# picoAva-Rev3.net
KiCad netlist of a schematic drawn in EAGLE
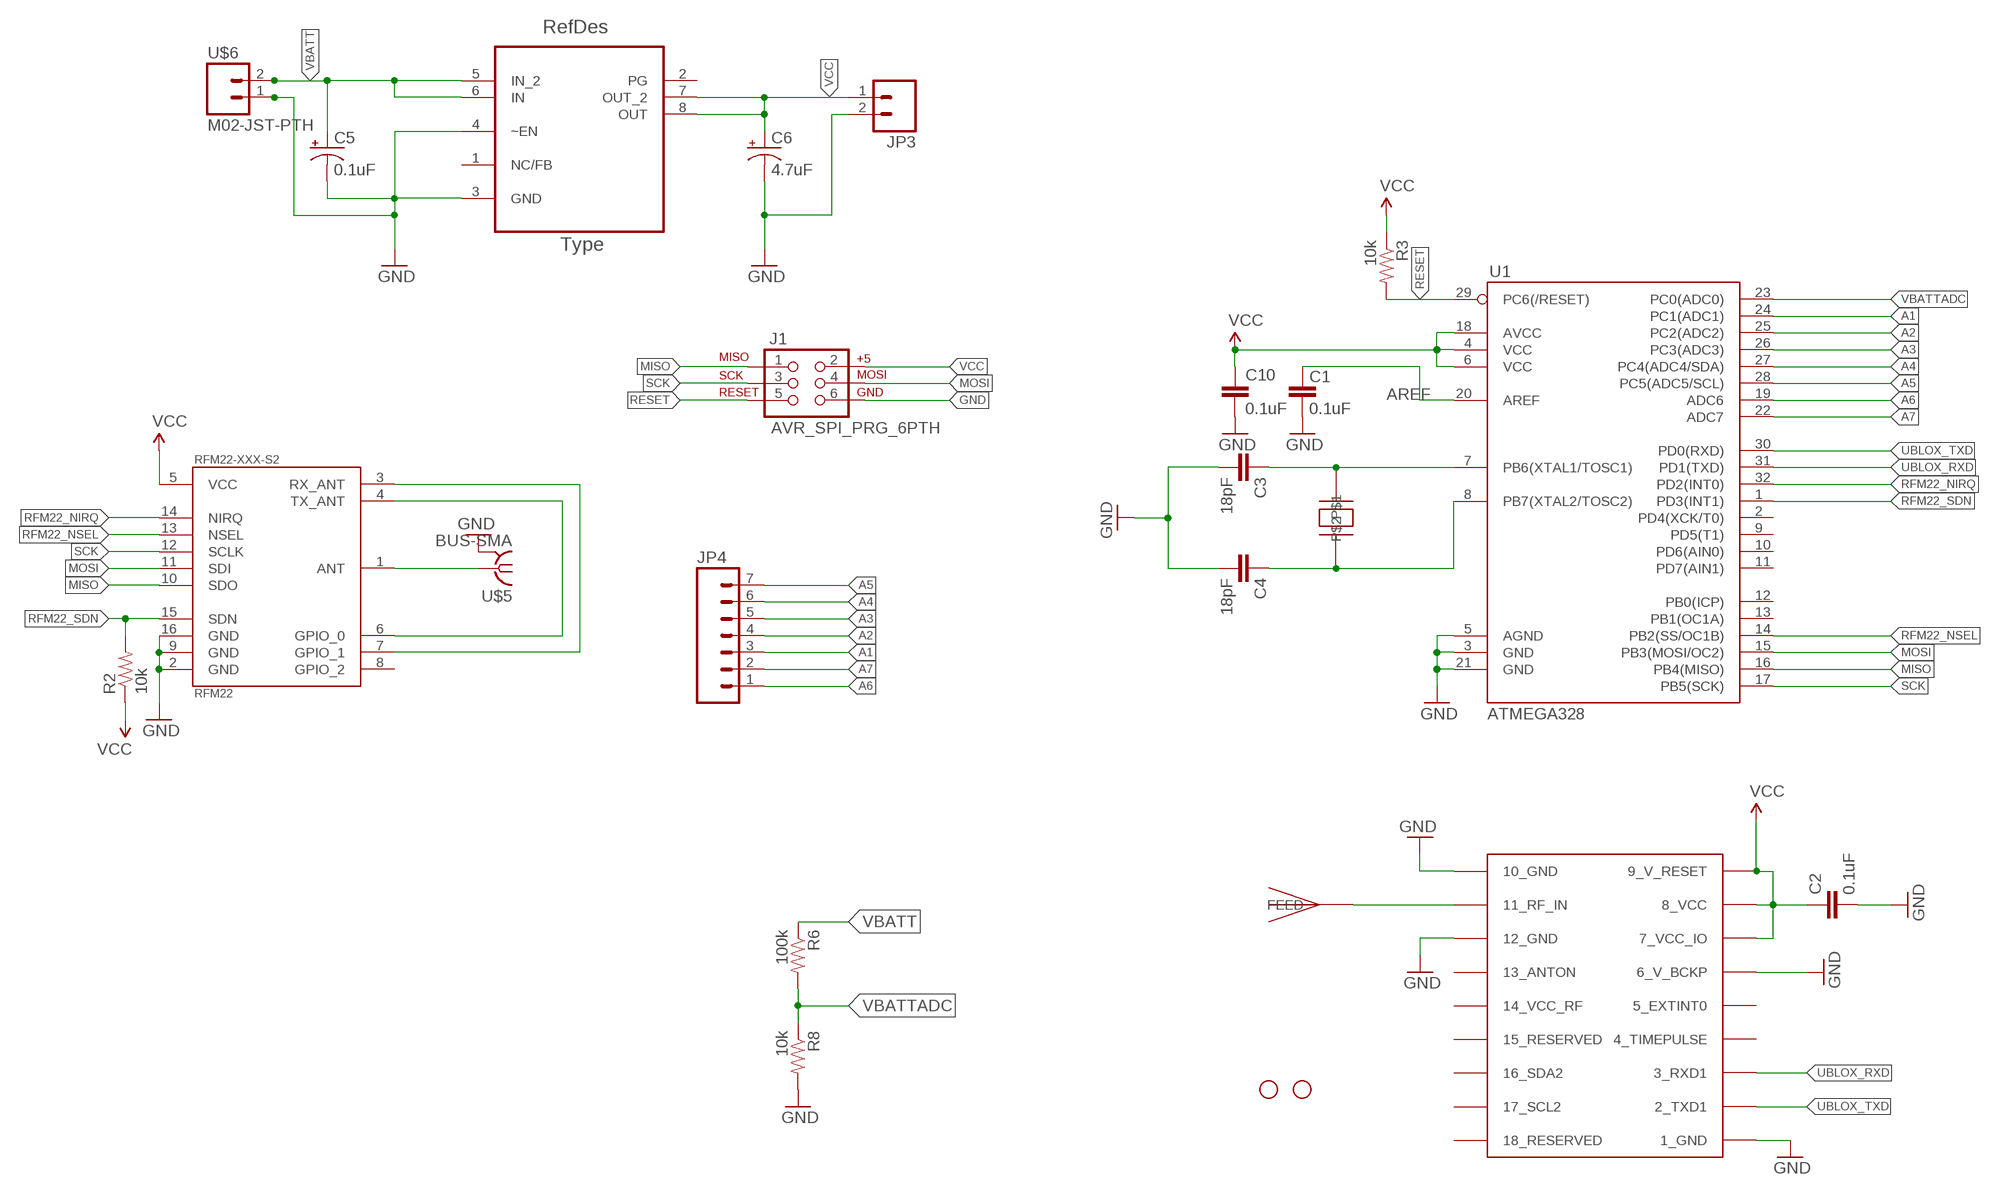
[diagram p0: schematic, sheet 1]

(export (version "E")
  (design (tool "Eeschema 10.0.6"))
  (components
    (comp (ref "C1")
      (value "0.1uF")
      (footprint "eagle-import:0402-CAP")
      (libsource (lib "eagle-import") (part "CAP0402-CAP"))
    )
    (comp (ref "C2")
      (value "0.1uF")
      (footprint "eagle-import:0402-CAP")
      (libsource (lib "eagle-import") (part "CAP0402-CAP"))
    )
    (comp (ref "C3")
      (value "18pF")
      (footprint "eagle-import:0402-CAP")
      (libsource (lib "eagle-import") (part "CAP0402-CAP"))
    )
    (comp (ref "C4")
      (value "18pF")
      (footprint "eagle-import:0402-CAP")
      (libsource (lib "eagle-import") (part "CAP0402-CAP"))
    )
    (comp (ref "C5")
      (value "0.1uF")
      (footprint "eagle-import:EIA3216-KIT")
      (libsource (lib "eagle-import") (part "CAP_POL1206-KIT"))
    )
    (comp (ref "C6")
      (value "4.7uF")
      (footprint "eagle-import:EIA3216-KIT")
      (libsource (lib "eagle-import") (part "CAP_POL1206-KIT"))
    )
    (comp (ref "C10")
      (value "0.1uF")
      (footprint "eagle-import:0402-CAP")
      (libsource (lib "eagle-import") (part "CAP0402-CAP"))
    )
    (comp (ref "J1")
      (value "AVR_SPI_PRG_6PTH")
      (footprint "eagle-import:2X3")
      (libsource (lib "eagle-import") (part "AVR_SPI_PRG_6PTH"))
    )
    (comp (ref "JP1")
      (value "STAND-OFF")
      (footprint "eagle-import:STAND-OFF")
      (libsource (lib "eagle-import") (part "STAND-OFF"))
    )
    (comp (ref "JP2")
      (value "STAND-OFF")
      (footprint "eagle-import:STAND-OFF")
      (libsource (lib "eagle-import") (part "STAND-OFF"))
    )
    (comp (ref "JP3")
      (value "M02PTH")
      (footprint "eagle-import:1X02")
      (libsource (lib "eagle-import") (part "M02PTH"))
    )
    (comp (ref "JP4")
      (value "M07")
      (footprint "eagle-import:1X07")
      (libsource (lib "eagle-import") (part "M07"))
    )
    (comp (ref "R2")
      (value "10k")
      (footprint "eagle-import:0402-RES")
      (libsource (lib "eagle-import") (part "RESISTOR0402-RES"))
    )
    (comp (ref "R3")
      (value "10k")
      (footprint "eagle-import:0402-RES")
      (libsource (lib "eagle-import") (part "RESISTOR0402-RES"))
    )
    (comp (ref "R6")
      (value "100k")
      (footprint "eagle-import:0402-RES")
      (libsource (lib "eagle-import") (part "RESISTOR0402-RES"))
    )
    (comp (ref "R8")
      (value "10k")
      (footprint "eagle-import:0402-RES")
      (libsource (lib "eagle-import") (part "RESISTOR0402-RES"))
    )
    (comp (ref "RFM22-XXX-S2")
      (value "RFM22")
      (footprint "eagle-import:RFM22-XXX-S2")
      (libsource (lib "eagle-import") (part "RFM22"))
    )
    (comp (ref "U$1")
      (value "UBLOX_MAX-6")
      (footprint "eagle-import:UBLOX_MAX-6")
      (libsource (lib "eagle-import") (part "UBLOX_MAX-6"))
    )
    (comp (ref "U$2")
      (value "ABRACON_ABM3_CRYSTAL")
      (footprint "eagle-import:ABRACON_ABM3_CRYSTAL")
      (libsource (lib "eagle-import") (part "ABRACON_ABM3_CRYSTAL"))
    )
    (comp (ref "U$3")
      (value "JTI_ANTENNA-1575AT43A40")
      (footprint "eagle-import:JTI_ANTENNA-1575AT43A40")
      (libsource (lib "eagle-import") (part "JTI_ANTENNA-1575AT43A40"))
    )
    (comp (ref "U$5")
      (value "BUS-SMA")
      (footprint "eagle-import:BUS-SMA")
      (libsource (lib "eagle-import") (part "BUS-SMA"))
    )
    (comp (ref "U$6")
      (value "M02-JST-PTH")
      (footprint "eagle-import:M02-JST-PTH")
      (libsource (lib "eagle-import") (part "M02-JST-PTH"))
    )
    (comp (ref "U1")
      (value "ATMEGA328")
      (footprint "eagle-import:TQFP32-08")
      (libsource (lib "eagle-import") (part "ATMEGA168"))
    )
    (comp (ref "U2")
      (value "TPS76633D")
      (footprint "eagle-import:SOIC127P600X175-8N")
      (libsource (lib "eagle-import") (part "TPS76633D"))
    )
  )
  (nets
    (net (code "1") (name "/AREF") (class "Default")
      (node (ref "C1") (pin "2") (pinfunction "2_2") (pintype "passive"))
      (node (ref "U1") (pin "20") (pinfunction "AREF_20") (pintype "bidirectional"))
    )
    (net (code "2") (name "A1") (class "Default")
      (node (ref "JP4") (pin "3") (pinfunction "3_3") (pintype "passive"))
      (node (ref "U1") (pin "24") (pinfunction "PC1(ADC1)_24") (pintype "bidirectional"))
    )
    (net (code "3") (name "A2") (class "Default")
      (node (ref "JP4") (pin "4") (pinfunction "4_4") (pintype "passive"))
      (node (ref "U1") (pin "25") (pinfunction "PC2(ADC2)_25") (pintype "bidirectional"))
    )
    (net (code "4") (name "A3") (class "Default")
      (node (ref "JP4") (pin "5") (pinfunction "5_5") (pintype "passive"))
      (node (ref "U1") (pin "26") (pinfunction "PC3(ADC3)_26") (pintype "bidirectional"))
    )
    (net (code "5") (name "A4") (class "Default")
      (node (ref "JP4") (pin "6") (pinfunction "6_6") (pintype "passive"))
      (node (ref "U1") (pin "27") (pinfunction "PC4(ADC4/SDA)_27") (pintype "bidirectional"))
    )
    (net (code "6") (name "A5") (class "Default")
      (node (ref "JP4") (pin "7") (pinfunction "7_7") (pintype "passive"))
      (node (ref "U1") (pin "28") (pinfunction "PC5(ADC5/SCL)_28") (pintype "bidirectional"))
    )
    (net (code "7") (name "A6") (class "Default")
      (node (ref "JP4") (pin "1") (pinfunction "1_1") (pintype "passive"))
      (node (ref "U1") (pin "19") (pinfunction "ADC6_19") (pintype "bidirectional"))
    )
    (net (code "8") (name "A7") (class "Default")
      (node (ref "JP4") (pin "2") (pinfunction "2_2") (pintype "passive"))
      (node (ref "U1") (pin "22") (pinfunction "ADC7_22") (pintype "bidirectional"))
    )
    (net (code "9") (name "GND") (class "Default")
      (node (ref "C1") (pin "1") (pinfunction "1_1") (pintype "passive"))
      (node (ref "C10") (pin "2") (pinfunction "2_2") (pintype "passive"))
      (node (ref "C2") (pin "2") (pinfunction "2_2") (pintype "passive"))
      (node (ref "C3") (pin "2") (pinfunction "2_2") (pintype "passive"))
      (node (ref "C4") (pin "2") (pinfunction "2_2") (pintype "passive"))
      (node (ref "C5") (pin "C") (pinfunction "-_C") (pintype "passive"))
      (node (ref "C6") (pin "C") (pinfunction "-_C") (pintype "passive"))
      (node (ref "J1") (pin "6") (pinfunction "6_6") (pintype "passive"))
      (node (ref "JP3") (pin "2") (pinfunction "2_2") (pintype "passive"))
      (node (ref "R8") (pin "2") (pinfunction "2_2") (pintype "passive"))
      (node (ref "RFM22-XXX-S2") (pin "16") (pinfunction "GND_16") (pintype "power_in"))
      (node (ref "RFM22-XXX-S2") (pin "2") (pinfunction "GND_2") (pintype "power_in"))
      (node (ref "RFM22-XXX-S2") (pin "9") (pinfunction "GND_9") (pintype "power_in"))
      (node (ref "U$1") (pin "10_GND") (pinfunction "10_GND_10_GND") (pintype "bidirectional"))
      (node (ref "U$1") (pin "12_GND") (pinfunction "12_GND_12_GND") (pintype "bidirectional"))
      (node (ref "U$1") (pin "1_GND") (pinfunction "1_GND_1_GND") (pintype "bidirectional"))
      (node (ref "U$1") (pin "6_V_BCKP") (pinfunction "6_V_BCKP_6_V_BCKP") (pintype "bidirectional"))
      (node (ref "U$5") (pin "2") (pinfunction "GND_2") (pintype "power_in"))
      (node (ref "U$5") (pin "3") (pinfunction "GND_3") (pintype "power_in"))
      (node (ref "U$5") (pin "4") (pinfunction "GND_4") (pintype "power_in"))
      (node (ref "U$5") (pin "5") (pinfunction "GND_5") (pintype "power_in"))
      (node (ref "U$6") (pin "1") (pinfunction "1_1") (pintype "passive"))
      (node (ref "U1") (pin "21") (pinfunction "GND_21") (pintype "bidirectional"))
      (node (ref "U1") (pin "3") (pinfunction "GND_3") (pintype "bidirectional"))
      (node (ref "U1") (pin "5") (pinfunction "AGND_5") (pintype "bidirectional"))
      (node (ref "U2") (pin "3") (pinfunction "GND_3") (pintype "passive"))
      (node (ref "U2") (pin "4") (pinfunction "~{EN}_4") (pintype "input"))
    )
    (net (code "10") (name "MISO") (class "Default")
      (node (ref "J1") (pin "1") (pinfunction "1_1") (pintype "passive"))
      (node (ref "RFM22-XXX-S2") (pin "10") (pinfunction "SDO_10") (pintype "output"))
      (node (ref "U1") (pin "16") (pinfunction "PB4(MISO)_16") (pintype "bidirectional"))
    )
    (net (code "11") (name "MOSI") (class "Default")
      (node (ref "J1") (pin "4") (pinfunction "4_4") (pintype "passive"))
      (node (ref "RFM22-XXX-S2") (pin "11") (pinfunction "SDI_11") (pintype "input"))
      (node (ref "U1") (pin "15") (pinfunction "PB3(MOSI/OC2)_15") (pintype "bidirectional"))
    )
    (net (code "12") (name "Net-(RFM22-XXX-S2-ANT)") (class "Default")
      (node (ref "RFM22-XXX-S2") (pin "1") (pinfunction "ANT_1") (pintype "bidirectional"))
      (node (ref "U$5") (pin "1") (pinfunction "1_1") (pintype "passive"))
    )
    (net (code "13") (name "Net-(RFM22-XXX-S2-GPIO_0)") (class "Default")
      (node (ref "RFM22-XXX-S2") (pin "4") (pinfunction "TX_ANT_4") (pintype "input"))
      (node (ref "RFM22-XXX-S2") (pin "6") (pinfunction "GPIO_0_6") (pintype "bidirectional"))
    )
    (net (code "14") (name "Net-(RFM22-XXX-S2-GPIO_1)") (class "Default")
      (node (ref "RFM22-XXX-S2") (pin "3") (pinfunction "RX_ANT_3") (pintype "input"))
      (node (ref "RFM22-XXX-S2") (pin "7") (pinfunction "GPIO_1_7") (pintype "bidirectional"))
    )
    (net (code "15") (name "Net-(U$1-Pad11_RF_IN)") (class "Default")
      (node (ref "U$1") (pin "11_RF_IN") (pinfunction "11_RF_IN_11_RF_IN") (pintype "bidirectional"))
      (node (ref "U$3") (pin "FEED") (pinfunction "FEED_FEED") (pintype "bidirectional"))
    )
    (net (code "16") (name "Net-(U1-PB6(XTAL1{slash}TOSC1))") (class "Default")
      (node (ref "C3") (pin "1") (pinfunction "1_1") (pintype "passive"))
      (node (ref "U$2") (pin "P$2") (pinfunction "P$2_P$2") (pintype "bidirectional"))
      (node (ref "U1") (pin "7") (pinfunction "PB6(XTAL1/TOSC1)_7") (pintype "bidirectional"))
    )
    (net (code "17") (name "Net-(U1-PB7(XTAL2{slash}TOSC2))") (class "Default")
      (node (ref "C4") (pin "1") (pinfunction "1_1") (pintype "passive"))
      (node (ref "U$2") (pin "P$1") (pinfunction "P$1_P$1") (pintype "bidirectional"))
      (node (ref "U1") (pin "8") (pinfunction "PB7(XTAL2/TOSC2)_8") (pintype "bidirectional"))
    )
    (net (code "18") (name "RESET") (class "Default")
      (node (ref "J1") (pin "5") (pinfunction "5_5") (pintype "passive"))
      (node (ref "R3") (pin "2") (pinfunction "2_2") (pintype "passive"))
      (node (ref "U1") (pin "29") (pinfunction "PC6(/RESET)_29") (pintype "bidirectional"))
    )
    (net (code "19") (name "RFM22_NIRQ") (class "Default")
      (node (ref "RFM22-XXX-S2") (pin "14") (pinfunction "NIRQ_14") (pintype "output"))
      (node (ref "U1") (pin "32") (pinfunction "PD2(INT0)_32") (pintype "bidirectional"))
    )
    (net (code "20") (name "RFM22_NSEL") (class "Default")
      (node (ref "RFM22-XXX-S2") (pin "13") (pinfunction "NSEL_13") (pintype "input"))
      (node (ref "U1") (pin "14") (pinfunction "PB2(SS/OC1B)_14") (pintype "bidirectional"))
    )
    (net (code "21") (name "RFM22_SDN") (class "Default")
      (node (ref "R2") (pin "2") (pinfunction "2_2") (pintype "passive"))
      (node (ref "RFM22-XXX-S2") (pin "15") (pinfunction "SDN_15") (pintype "input"))
      (node (ref "U1") (pin "1") (pinfunction "PD3(INT1)_1") (pintype "bidirectional"))
    )
    (net (code "22") (name "SCK") (class "Default")
      (node (ref "J1") (pin "3") (pinfunction "3_3") (pintype "passive"))
      (node (ref "RFM22-XXX-S2") (pin "12") (pinfunction "SCLK_12") (pintype "input"))
      (node (ref "U1") (pin "17") (pinfunction "PB5(SCK)_17") (pintype "bidirectional"))
    )
    (net (code "23") (name "UBLOX_RXD") (class "Default")
      (node (ref "U$1") (pin "3_RXD1") (pinfunction "3_RXD1_3_RXD1") (pintype "bidirectional"))
      (node (ref "U1") (pin "31") (pinfunction "PD1(TXD)_31") (pintype "bidirectional"))
    )
    (net (code "24") (name "UBLOX_TXD") (class "Default")
      (node (ref "U$1") (pin "2_TXD1") (pinfunction "2_TXD1_2_TXD1") (pintype "bidirectional"))
      (node (ref "U1") (pin "30") (pinfunction "PD0(RXD)_30") (pintype "bidirectional"))
    )
    (net (code "25") (name "VBATT") (class "Default")
      (node (ref "C5") (pin "A") (pinfunction "+_A") (pintype "passive"))
      (node (ref "R6") (pin "1") (pinfunction "1_1") (pintype "passive"))
      (node (ref "U$6") (pin "2") (pinfunction "2_2") (pintype "passive"))
      (node (ref "U2") (pin "5") (pinfunction "IN_2_5") (pintype "input"))
      (node (ref "U2") (pin "6") (pinfunction "IN_6") (pintype "input"))
    )
    (net (code "26") (name "VBATTADC") (class "Default")
      (node (ref "R6") (pin "2") (pinfunction "2_2") (pintype "passive"))
      (node (ref "R8") (pin "1") (pinfunction "1_1") (pintype "passive"))
      (node (ref "U1") (pin "23") (pinfunction "PC0(ADC0)_23") (pintype "bidirectional"))
    )
    (net (code "27") (name "VCC") (class "Default")
      (node (ref "C10") (pin "1") (pinfunction "1_1") (pintype "passive"))
      (node (ref "C2") (pin "1") (pinfunction "1_1") (pintype "passive"))
      (node (ref "C6") (pin "A") (pinfunction "+_A") (pintype "passive"))
      (node (ref "J1") (pin "2") (pinfunction "2_2") (pintype "passive"))
      (node (ref "JP3") (pin "1") (pinfunction "1_1") (pintype "passive"))
      (node (ref "R2") (pin "1") (pinfunction "1_1") (pintype "passive"))
      (node (ref "R3") (pin "1") (pinfunction "1_1") (pintype "passive"))
      (node (ref "RFM22-XXX-S2") (pin "5") (pinfunction "VCC_5") (pintype "bidirectional"))
      (node (ref "U$1") (pin "7_VCC_IO") (pinfunction "7_VCC_IO_7_VCC_IO") (pintype "bidirectional"))
      (node (ref "U$1") (pin "8_VCC") (pinfunction "8_VCC_8_VCC") (pintype "bidirectional"))
      (node (ref "U$1") (pin "9_V_RESET") (pinfunction "9_V_RESET_9_V_RESET") (pintype "bidirectional"))
      (node (ref "U1") (pin "18") (pinfunction "AVCC_18") (pintype "bidirectional"))
      (node (ref "U1") (pin "4") (pinfunction "VCC_4") (pintype "bidirectional"))
      (node (ref "U1") (pin "6") (pinfunction "VCC_6") (pintype "bidirectional"))
      (node (ref "U2") (pin "7") (pinfunction "OUT_2_7") (pintype "output"))
      (node (ref "U2") (pin "8") (pinfunction "OUT_8") (pintype "output"))
    )
    (net (code "28") (name "unconnected-(RFM22-XXX-S2-GPIO_2-Pad8)") (class "Default")
      (node (ref "RFM22-XXX-S2") (pin "8") (pinfunction "GPIO_2_8") (pintype "bidirectional"))
    )
    (net (code "29") (name "unconnected-(U$1-Pad4_TIMEPULSE)") (class "Default")
      (node (ref "U$1") (pin "4_TIMEPULSE") (pinfunction "4_TIMEPULSE_4_TIMEPULSE") (pintype "bidirectional"))
    )
    (net (code "30") (name "unconnected-(U$1-Pad5_EXTINT0)") (class "Default")
      (node (ref "U$1") (pin "5_EXTINT0") (pinfunction "5_EXTINT0_5_EXTINT0") (pintype "bidirectional"))
    )
    (net (code "31") (name "unconnected-(U$1-Pad13_ANTON)") (class "Default")
      (node (ref "U$1") (pin "13_ANTON") (pinfunction "13_ANTON_13_ANTON") (pintype "bidirectional"))
    )
    (net (code "32") (name "unconnected-(U$1-Pad14_VCC_RF)") (class "Default")
      (node (ref "U$1") (pin "14_VCC_RF") (pinfunction "14_VCC_RF_14_VCC_RF") (pintype "bidirectional"))
    )
    (net (code "33") (name "unconnected-(U$1-Pad15_RESERVED)") (class "Default")
      (node (ref "U$1") (pin "15_RESERVED") (pinfunction "15_RESERVED_15_RESERVED") (pintype "bidirectional"))
    )
    (net (code "34") (name "unconnected-(U$1-Pad16_SDA2)") (class "Default")
      (node (ref "U$1") (pin "16_SDA2") (pinfunction "16_SDA2_16_SDA2") (pintype "bidirectional"))
    )
    (net (code "35") (name "unconnected-(U$1-Pad17_SCL2)") (class "Default")
      (node (ref "U$1") (pin "17_SCL2") (pinfunction "17_SCL2_17_SCL2") (pintype "bidirectional"))
    )
    (net (code "36") (name "unconnected-(U$1-Pad18_RESERVED)") (class "Default")
      (node (ref "U$1") (pin "18_RESERVED") (pinfunction "18_RESERVED_18_RESERVED") (pintype "bidirectional"))
    )
    (net (code "37") (name "unconnected-(U1-PB0(ICP)-Pad12)") (class "Default")
      (node (ref "U1") (pin "12") (pinfunction "PB0(ICP)_12") (pintype "bidirectional"))
    )
    (net (code "38") (name "unconnected-(U1-PB1(OC1A)-Pad13)") (class "Default")
      (node (ref "U1") (pin "13") (pinfunction "PB1(OC1A)_13") (pintype "bidirectional"))
    )
    (net (code "39") (name "unconnected-(U1-PD4(XCK{slash}T0)-Pad2)") (class "Default")
      (node (ref "U1") (pin "2") (pinfunction "PD4(XCK/T0)_2") (pintype "bidirectional"))
    )
    (net (code "40") (name "unconnected-(U1-PD5(T1)-Pad9)") (class "Default")
      (node (ref "U1") (pin "9") (pinfunction "PD5(T1)_9") (pintype "bidirectional"))
    )
    (net (code "41") (name "unconnected-(U1-PD6(AIN0)-Pad10)") (class "Default")
      (node (ref "U1") (pin "10") (pinfunction "PD6(AIN0)_10") (pintype "bidirectional"))
    )
    (net (code "42") (name "unconnected-(U1-PD7(AIN1)-Pad11)") (class "Default")
      (node (ref "U1") (pin "11") (pinfunction "PD7(AIN1)_11") (pintype "bidirectional"))
    )
    (net (code "43") (name "unconnected-(U2-NC{slash}FB-Pad1)") (class "Default")
      (node (ref "U2") (pin "1") (pinfunction "NC/FB_1") (pintype "no_connect"))
    )
    (net (code "44") (name "unconnected-(U2-PG-Pad2)") (class "Default")
      (node (ref "U2") (pin "2") (pinfunction "PG_2") (pintype "output"))
    )
  )
)
